# BLOCK4.net
KiCad netlist of a schematic drawn in Altium Designer
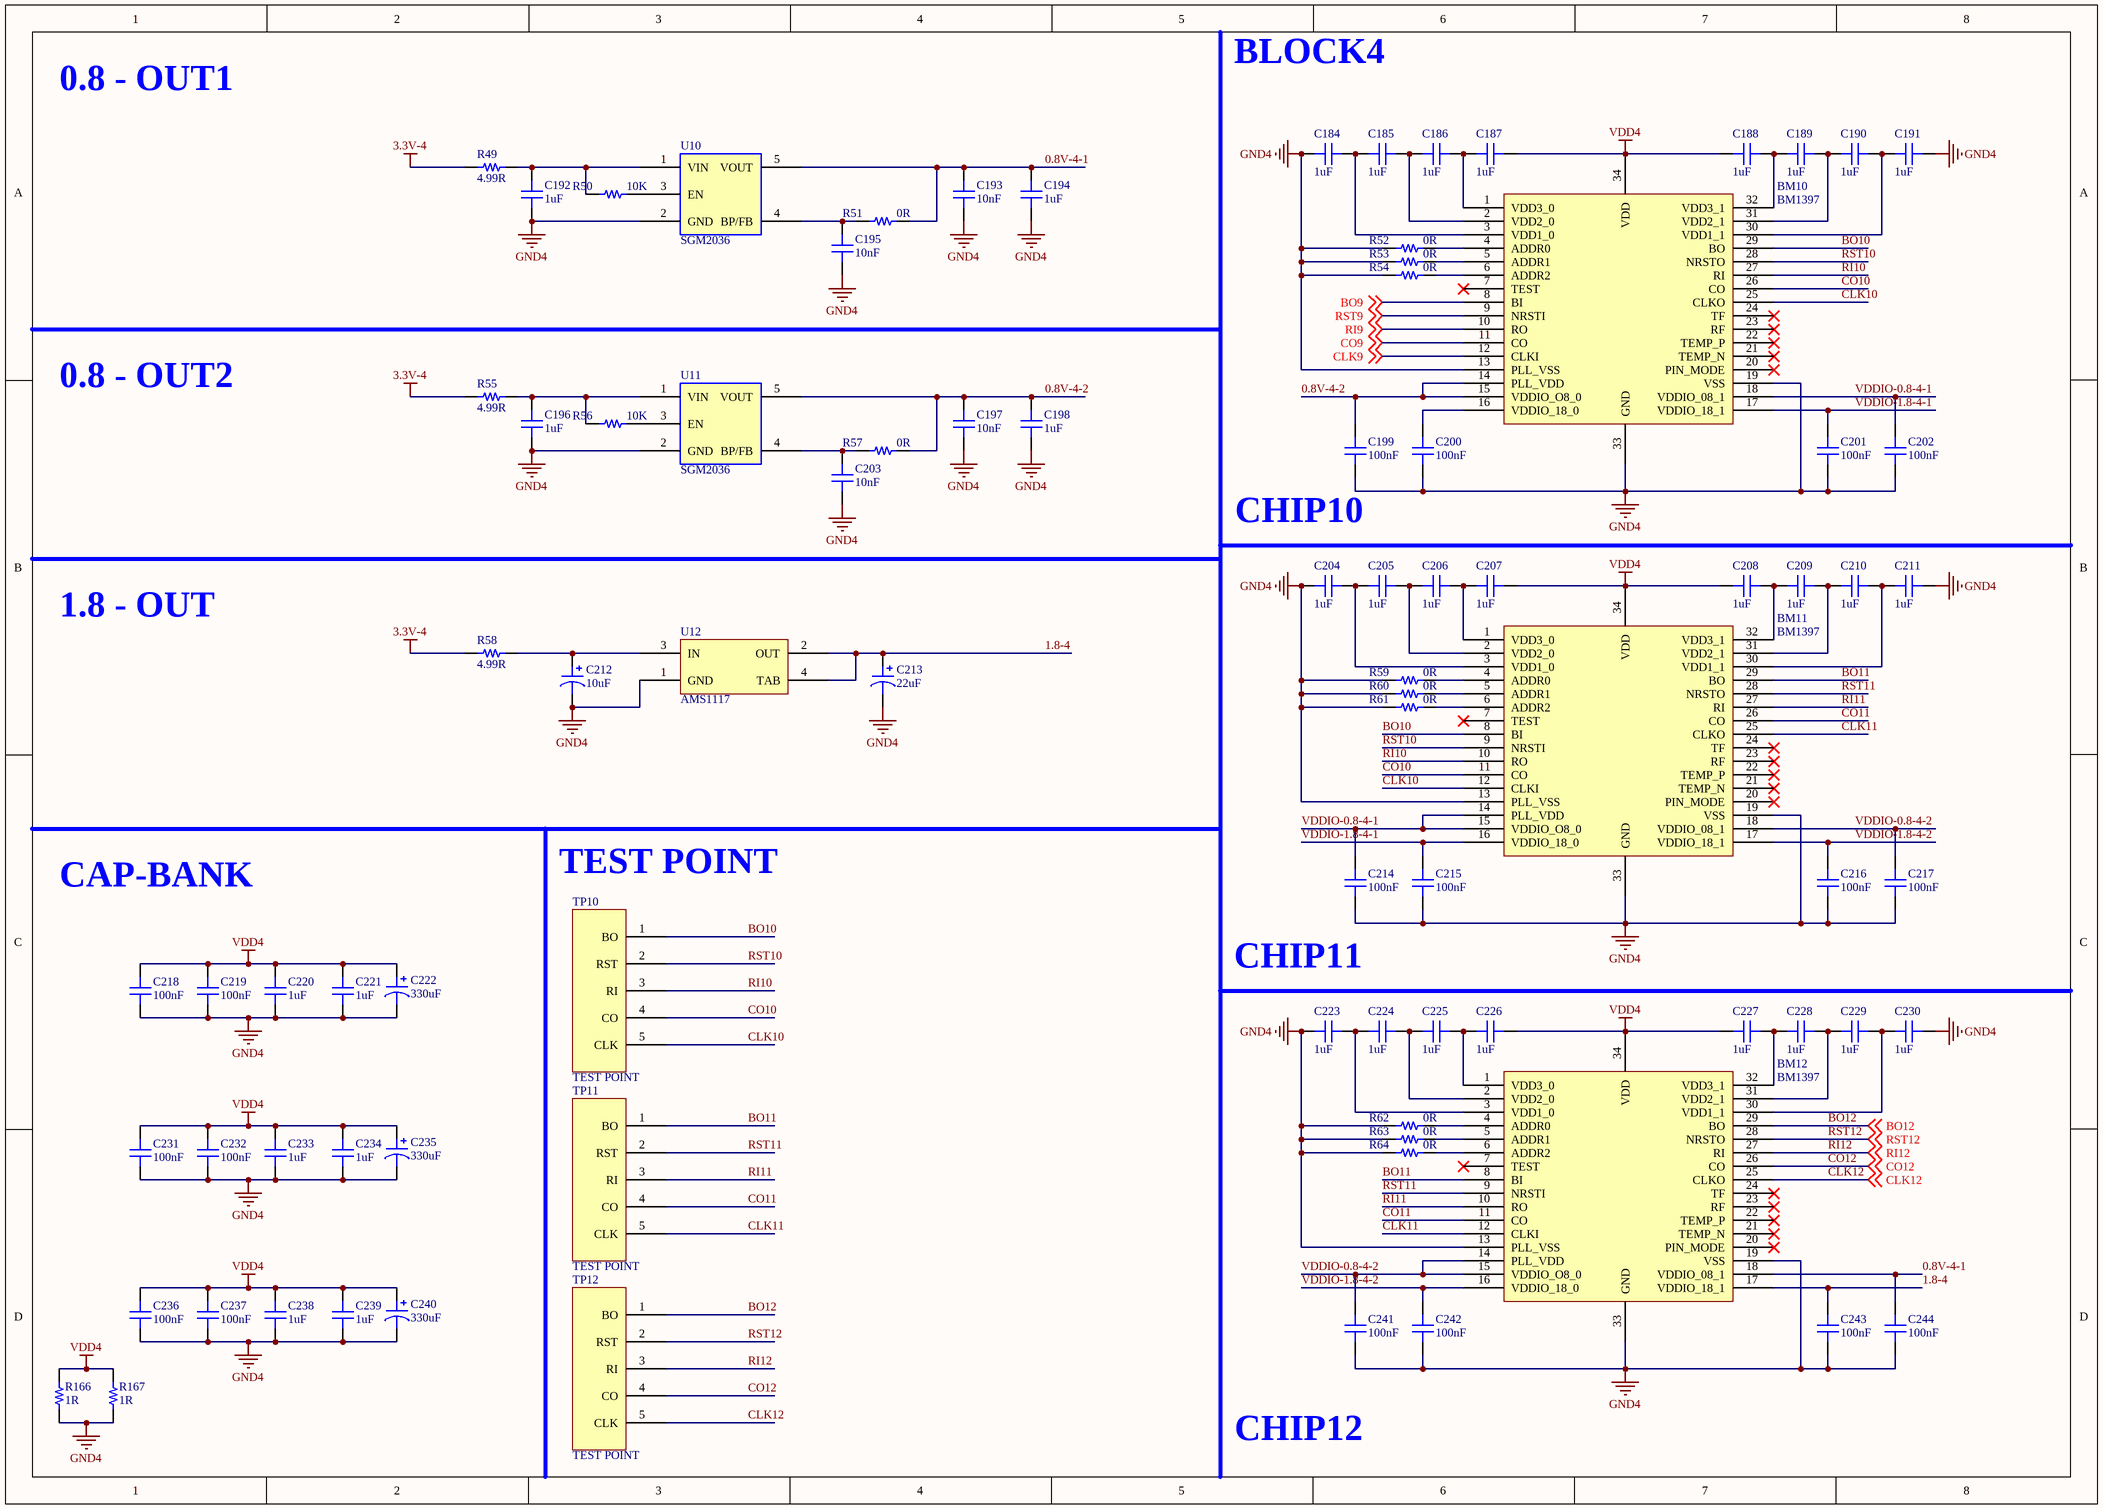
[diagram p0: BLOCK4.SchDoc]

(export (version "E")
  (design (tool "Eeschema 10.0.6"))
  (components
    (comp (ref "BM10") (value "BM1397") (footprint "BM1387") (libsource (lib "Miner_8TH") (part "BM1397_1")))
    (comp (ref "BM11") (value "BM1397") (footprint "BM1387") (libsource (lib "Miner_8TH") (part "BM1397_1")))
    (comp (ref "BM12") (value "BM1397") (footprint "BM1387") (libsource (lib "Miner_8TH") (part "BM1397_1")))
    (comp (ref "C184") (value "1uF") (footprint "CAP-SMD-0603") (libsource (lib "Miner_8TH") (part "CAP")))
    (comp (ref "C185") (value "1uF") (footprint "CAP-SMD-0603") (libsource (lib "Miner_8TH") (part "CAP")))
    (comp (ref "C186") (value "1uF") (footprint "CAP-SMD-0603") (libsource (lib "Miner_8TH") (part "CAP")))
    (comp (ref "C187") (value "1uF") (footprint "CAP-SMD-0603") (libsource (lib "Miner_8TH") (part "CAP")))
    (comp (ref "C188") (value "1uF") (footprint "CAP-SMD-0603") (libsource (lib "Miner_8TH") (part "CAP")))
    (comp (ref "C189") (value "1uF") (footprint "CAP-SMD-0603") (libsource (lib "Miner_8TH") (part "CAP")))
    (comp (ref "C190") (value "1uF") (footprint "CAP-SMD-0603") (libsource (lib "Miner_8TH") (part "CAP")))
    (comp (ref "C191") (value "1uF") (footprint "CAP-SMD-0603") (libsource (lib "Miner_8TH") (part "CAP")))
    (comp (ref "C192") (value "1uF") (footprint "CAP_SMD_0805") (libsource (lib "Miner_8TH") (part "CAP")))
    (comp (ref "C193") (value "10nF") (footprint "CAP_SMD_0805") (libsource (lib "Miner_8TH") (part "CAP")))
    (comp (ref "C194") (value "1uF") (footprint "CAP_SMD_0805") (libsource (lib "Miner_8TH") (part "CAP")))
    (comp (ref "C195") (value "10nF") (footprint "CAP_SMD_0805") (libsource (lib "Miner_8TH") (part "CAP")))
    (comp (ref "C196") (value "1uF") (footprint "CAP_SMD_0805") (libsource (lib "Miner_8TH") (part "CAP")))
    (comp (ref "C197") (value "10nF") (footprint "CAP_SMD_0805") (libsource (lib "Miner_8TH") (part "CAP")))
    (comp (ref "C198") (value "1uF") (footprint "CAP_SMD_0805") (libsource (lib "Miner_8TH") (part "CAP")))
    (comp (ref "C199") (value "100nF") (footprint "CAP_SMD_0805") (libsource (lib "Miner_8TH") (part "CAP")))
    (comp (ref "C200") (value "100nF") (footprint "CAP_SMD_0805") (libsource (lib "Miner_8TH") (part "CAP")))
    (comp (ref "C201") (value "100nF") (footprint "CAP_SMD_0805") (libsource (lib "Miner_8TH") (part "CAP")))
    (comp (ref "C202") (value "100nF") (footprint "CAP_SMD_0805") (libsource (lib "Miner_8TH") (part "CAP")))
    (comp (ref "C203") (value "10nF") (footprint "CAP_SMD_0805") (libsource (lib "Miner_8TH") (part "CAP")))
    (comp (ref "C204") (value "1uF") (footprint "CAP-SMD-0603") (libsource (lib "Miner_8TH") (part "CAP")))
    (comp (ref "C205") (value "1uF") (footprint "CAP-SMD-0603") (libsource (lib "Miner_8TH") (part "CAP")))
    (comp (ref "C206") (value "1uF") (footprint "CAP-SMD-0603") (libsource (lib "Miner_8TH") (part "CAP")))
    (comp (ref "C207") (value "1uF") (footprint "CAP-SMD-0603") (libsource (lib "Miner_8TH") (part "CAP")))
    (comp (ref "C208") (value "1uF") (footprint "CAP-SMD-0603") (libsource (lib "Miner_8TH") (part "CAP")))
    (comp (ref "C209") (value "1uF") (footprint "CAP-SMD-0603") (libsource (lib "Miner_8TH") (part "CAP")))
    (comp (ref "C210") (value "1uF") (footprint "CAP-SMD-0603") (libsource (lib "Miner_8TH") (part "CAP")))
    (comp (ref "C211") (value "1uF") (footprint "CAP-SMD-0603") (libsource (lib "Miner_8TH") (part "CAP")))
    (comp (ref "C212")
      (value "10uF")
      (footprint "CAP-TAN-CASE-A")
      (libsource (lib "Miner_8TH") (part "POLARIZED CAP"))
    )
    (comp (ref "C213")
      (value "22uF")
      (footprint "CAP-TAN-CASE-A")
      (libsource (lib "Miner_8TH") (part "POLARIZED CAP"))
    )
    (comp (ref "C214") (value "100nF") (footprint "CAP_SMD_0805") (libsource (lib "Miner_8TH") (part "CAP")))
    (comp (ref "C215") (value "100nF") (footprint "CAP_SMD_0805") (libsource (lib "Miner_8TH") (part "CAP")))
    (comp (ref "C216") (value "100nF") (footprint "CAP_SMD_0805") (libsource (lib "Miner_8TH") (part "CAP")))
    (comp (ref "C217") (value "100nF") (footprint "CAP_SMD_0805") (libsource (lib "Miner_8TH") (part "CAP")))
    (comp (ref "C218") (value "100nF") (footprint "CAP_SMD_0805") (libsource (lib "Miner_8TH") (part "CAP")))
    (comp (ref "C219") (value "100nF") (footprint "CAP_SMD_0805") (libsource (lib "Miner_8TH") (part "CAP")))
    (comp (ref "C220") (value "1uF") (footprint "CAP_SMD_0805") (libsource (lib "Miner_8TH") (part "CAP")))
    (comp (ref "C221") (value "1uF") (footprint "CAP_SMD_0805") (libsource (lib "Miner_8TH") (part "CAP")))
    (comp (ref "C222")
      (value "330uF")
      (footprint "CAP-TAN-CASE-E")
      (libsource (lib "Miner_8TH") (part "POLARIZED CAP"))
    )
    (comp (ref "C223") (value "1uF") (footprint "CAP-SMD-0603") (libsource (lib "Miner_8TH") (part "CAP")))
    (comp (ref "C224") (value "1uF") (footprint "CAP-SMD-0603") (libsource (lib "Miner_8TH") (part "CAP")))
    (comp (ref "C225") (value "1uF") (footprint "CAP-SMD-0603") (libsource (lib "Miner_8TH") (part "CAP")))
    (comp (ref "C226") (value "1uF") (footprint "CAP-SMD-0603") (libsource (lib "Miner_8TH") (part "CAP")))
    (comp (ref "C227") (value "1uF") (footprint "CAP-SMD-0603") (libsource (lib "Miner_8TH") (part "CAP")))
    (comp (ref "C228") (value "1uF") (footprint "CAP-SMD-0603") (libsource (lib "Miner_8TH") (part "CAP")))
    (comp (ref "C229") (value "1uF") (footprint "CAP-SMD-0603") (libsource (lib "Miner_8TH") (part "CAP")))
    (comp (ref "C230") (value "1uF") (footprint "CAP-SMD-0603") (libsource (lib "Miner_8TH") (part "CAP")))
    (comp (ref "C231") (value "100nF") (footprint "CAP_SMD_0805") (libsource (lib "Miner_8TH") (part "CAP")))
    (comp (ref "C232") (value "100nF") (footprint "CAP_SMD_0805") (libsource (lib "Miner_8TH") (part "CAP")))
    (comp (ref "C233") (value "1uF") (footprint "CAP_SMD_0805") (libsource (lib "Miner_8TH") (part "CAP")))
    (comp (ref "C234") (value "1uF") (footprint "CAP_SMD_0805") (libsource (lib "Miner_8TH") (part "CAP")))
    (comp (ref "C235")
      (value "330uF")
      (footprint "CAP-TAN-CASE-E")
      (libsource (lib "Miner_8TH") (part "POLARIZED CAP"))
    )
    (comp (ref "C236") (value "100nF") (footprint "CAP_SMD_0805") (libsource (lib "Miner_8TH") (part "CAP")))
    (comp (ref "C237") (value "100nF") (footprint "CAP_SMD_0805") (libsource (lib "Miner_8TH") (part "CAP")))
    (comp (ref "C238") (value "1uF") (footprint "CAP_SMD_0805") (libsource (lib "Miner_8TH") (part "CAP")))
    (comp (ref "C239") (value "1uF") (footprint "CAP_SMD_0805") (libsource (lib "Miner_8TH") (part "CAP")))
    (comp (ref "C240")
      (value "330uF")
      (footprint "CAP-TAN-CASE-E")
      (libsource (lib "Miner_8TH") (part "POLARIZED CAP"))
    )
    (comp (ref "C241") (value "100nF") (footprint "CAP_SMD_0805") (libsource (lib "Miner_8TH") (part "CAP")))
    (comp (ref "C242") (value "100nF") (footprint "CAP_SMD_0805") (libsource (lib "Miner_8TH") (part "CAP")))
    (comp (ref "C243") (value "100nF") (footprint "CAP_SMD_0805") (libsource (lib "Miner_8TH") (part "CAP")))
    (comp (ref "C244") (value "100nF") (footprint "CAP_SMD_0805") (libsource (lib "Miner_8TH") (part "CAP")))
    (comp (ref "R49") (value "4.99R") (footprint "RES-SMD-1206") (libsource (lib "Miner_8TH") (part "RES")))
    (comp (ref "R50") (value "10K") (footprint "RES-SMD-0402") (libsource (lib "Miner_8TH") (part "RES")))
    (comp (ref "R51") (value "0R") (footprint "RES-SMD-0402") (libsource (lib "Miner_8TH") (part "RES")))
    (comp (ref "R52") (value "0R") (footprint "RES-SMD-0402") (libsource (lib "Miner_8TH") (part "RES")))
    (comp (ref "R53") (value "0R") (footprint "RES-SMD-0402") (libsource (lib "Miner_8TH") (part "RES")))
    (comp (ref "R54") (value "0R") (footprint "RES-SMD-0402") (libsource (lib "Miner_8TH") (part "RES")))
    (comp (ref "R55") (value "4.99R") (footprint "RES-SMD-1206") (libsource (lib "Miner_8TH") (part "RES")))
    (comp (ref "R56") (value "10K") (footprint "RES-SMD-0402") (libsource (lib "Miner_8TH") (part "RES")))
    (comp (ref "R57") (value "0R") (footprint "RES-SMD-0402") (libsource (lib "Miner_8TH") (part "RES")))
    (comp (ref "R58") (value "4.99R") (footprint "RES-SMD-1206") (libsource (lib "Miner_8TH") (part "RES")))
    (comp (ref "R59") (value "0R") (footprint "RES-SMD-0402") (libsource (lib "Miner_8TH") (part "RES")))
    (comp (ref "R60") (value "0R") (footprint "RES-SMD-0402") (libsource (lib "Miner_8TH") (part "RES")))
    (comp (ref "R61") (value "0R") (footprint "RES-SMD-0402") (libsource (lib "Miner_8TH") (part "RES")))
    (comp (ref "R62") (value "0R") (footprint "RES-SMD-0402") (libsource (lib "Miner_8TH") (part "RES")))
    (comp (ref "R63") (value "0R") (footprint "RES-SMD-0402") (libsource (lib "Miner_8TH") (part "RES")))
    (comp (ref "R64") (value "0R") (footprint "RES-SMD-0402") (libsource (lib "Miner_8TH") (part "RES")))
    (comp (ref "R166") (value "1R") (footprint "RES-SMD-1210") (libsource (lib "Miner_8TH") (part "RES")))
    (comp (ref "R167") (value "1R") (footprint "RES-SMD-1210") (libsource (lib "Miner_8TH") (part "RES")))
    (comp (ref "TP10")
      (value "TEST POINT")
      (footprint "TEST_POINT")
      (libsource (lib "Miner_8TH") (part "TEST POINT"))
    )
    (comp (ref "TP11")
      (value "TEST POINT")
      (footprint "TEST_POINT")
      (libsource (lib "Miner_8TH") (part "TEST POINT"))
    )
    (comp (ref "TP12")
      (value "TEST POINT")
      (footprint "TEST_POINT")
      (libsource (lib "Miner_8TH") (part "TEST POINT"))
    )
    (comp (ref "U10")
      (value "SGM2036")
      (footprint "SOT23-5PIN")
      (libsource (lib "Miner_8TH") (part "SGM2036"))
    )
    (comp (ref "U11")
      (value "SGM2036")
      (footprint "SOT23-5PIN")
      (libsource (lib "Miner_8TH") (part "SGM2036"))
    )
    (comp (ref "U12") (value "AMS1117") (footprint "AMS1117") (libsource (lib "Miner_8TH") (part "AMS1117")))
  )
  (nets
    (net (code "1") (name "/0.8V-4-1") (class "Default")
      (node (ref "BM12") (pin "18") (pinfunction "VDDIO_08_1_18") (pintype "passive"))
      (node (ref "C193") (pin "2") (pinfunction "2_2") (pintype "passive"))
      (node (ref "C194") (pin "2") (pinfunction "2_2") (pintype "passive"))
      (node (ref "C244") (pin "2") (pinfunction "2_2") (pintype "passive"))
      (node (ref "R51") (pin "2") (pinfunction "2_2") (pintype "passive"))
      (node (ref "U10") (pin "5") (pinfunction "VOUT_5") (pintype "passive"))
    )
    (net (code "2") (name "/0.8V-4-2") (class "Default")
      (node (ref "BM10") (pin "14") (pinfunction "PLL_VDD_14") (pintype "passive"))
      (node (ref "BM10") (pin "15") (pinfunction "VDDIO_O8_0_15") (pintype "passive"))
      (node (ref "C197") (pin "2") (pinfunction "2_2") (pintype "passive"))
      (node (ref "C198") (pin "2") (pinfunction "2_2") (pintype "passive"))
      (node (ref "C199") (pin "2") (pinfunction "2_2") (pintype "passive"))
      (node (ref "R57") (pin "2") (pinfunction "2_2") (pintype "passive"))
      (node (ref "U11") (pin "5") (pinfunction "VOUT_5") (pintype "passive"))
    )
    (net (code "3") (name "/1.8-4") (class "Default")
      (node (ref "BM12") (pin "17") (pinfunction "VDDIO_18_1_17") (pintype "passive"))
      (node (ref "C213") (pin "1") (pinfunction "1_1") (pintype "passive"))
      (node (ref "C243") (pin "2") (pinfunction "2_2") (pintype "passive"))
      (node (ref "U12") (pin "2") (pinfunction "OUT_2") (pintype "passive"))
      (node (ref "U12") (pin "4") (pinfunction "TAB_4") (pintype "passive"))
    )
    (net (code "4") (name "/BO10") (class "Default")
      (node (ref "BM10") (pin "29") (pinfunction "BO_29") (pintype "passive"))
      (node (ref "BM11") (pin "8") (pinfunction "BI_8") (pintype "passive"))
      (node (ref "TP10") (pin "1") (pinfunction "BO_1") (pintype "passive"))
    )
    (net (code "5") (name "/BO11") (class "Default")
      (node (ref "BM11") (pin "29") (pinfunction "BO_29") (pintype "passive"))
      (node (ref "BM12") (pin "8") (pinfunction "BI_8") (pintype "passive"))
      (node (ref "TP11") (pin "1") (pinfunction "BO_1") (pintype "passive"))
    )
    (net (code "6") (name "/CLK10") (class "Default")
      (node (ref "BM10") (pin "25") (pinfunction "CLKO_25") (pintype "passive"))
      (node (ref "BM11") (pin "12") (pinfunction "CLKI_12") (pintype "passive"))
      (node (ref "TP10") (pin "5") (pinfunction "CLK_5") (pintype "passive"))
    )
    (net (code "7") (name "/CLK11") (class "Default")
      (node (ref "BM11") (pin "25") (pinfunction "CLKO_25") (pintype "passive"))
      (node (ref "BM12") (pin "12") (pinfunction "CLKI_12") (pintype "passive"))
      (node (ref "TP11") (pin "5") (pinfunction "CLK_5") (pintype "passive"))
    )
    (net (code "8") (name "/CO10") (class "Default")
      (node (ref "BM10") (pin "26") (pinfunction "CO_26") (pintype "passive"))
      (node (ref "BM11") (pin "11") (pinfunction "CO_11") (pintype "passive"))
      (node (ref "TP10") (pin "4") (pinfunction "CO_4") (pintype "passive"))
    )
    (net (code "9") (name "/CO11") (class "Default")
      (node (ref "BM11") (pin "26") (pinfunction "CO_26") (pintype "passive"))
      (node (ref "BM12") (pin "11") (pinfunction "CO_11") (pintype "passive"))
      (node (ref "TP11") (pin "4") (pinfunction "CO_4") (pintype "passive"))
    )
    (net (code "10") (name "/RI10") (class "Default")
      (node (ref "BM10") (pin "27") (pinfunction "RI_27") (pintype "passive"))
      (node (ref "BM11") (pin "10") (pinfunction "RO_10") (pintype "passive"))
      (node (ref "TP10") (pin "3") (pinfunction "RI_3") (pintype "passive"))
    )
    (net (code "11") (name "/RI11") (class "Default")
      (node (ref "BM11") (pin "27") (pinfunction "RI_27") (pintype "passive"))
      (node (ref "BM12") (pin "10") (pinfunction "RO_10") (pintype "passive"))
      (node (ref "TP11") (pin "3") (pinfunction "RI_3") (pintype "passive"))
    )
    (net (code "12") (name "/RST10") (class "Default")
      (node (ref "BM10") (pin "28") (pinfunction "NRSTO_28") (pintype "passive"))
      (node (ref "BM11") (pin "9") (pinfunction "NRSTI_9") (pintype "passive"))
      (node (ref "TP10") (pin "2") (pinfunction "RST_2") (pintype "passive"))
    )
    (net (code "13") (name "/RST11") (class "Default")
      (node (ref "BM11") (pin "28") (pinfunction "NRSTO_28") (pintype "passive"))
      (node (ref "BM12") (pin "9") (pinfunction "NRSTI_9") (pintype "passive"))
      (node (ref "TP11") (pin "2") (pinfunction "RST_2") (pintype "passive"))
    )
    (net (code "14") (name "/VDDIO-0.8-4-1") (class "Default")
      (node (ref "BM10") (pin "18") (pinfunction "VDDIO_08_1_18") (pintype "passive"))
      (node (ref "BM11") (pin "14") (pinfunction "PLL_VDD_14") (pintype "passive"))
      (node (ref "BM11") (pin "15") (pinfunction "VDDIO_O8_0_15") (pintype "passive"))
      (node (ref "C202") (pin "2") (pinfunction "2_2") (pintype "passive"))
      (node (ref "C214") (pin "2") (pinfunction "2_2") (pintype "passive"))
    )
    (net (code "15") (name "/VDDIO-0.8-4-2") (class "Default")
      (node (ref "BM11") (pin "18") (pinfunction "VDDIO_08_1_18") (pintype "passive"))
      (node (ref "BM12") (pin "14") (pinfunction "PLL_VDD_14") (pintype "passive"))
      (node (ref "BM12") (pin "15") (pinfunction "VDDIO_O8_0_15") (pintype "passive"))
      (node (ref "C217") (pin "2") (pinfunction "2_2") (pintype "passive"))
      (node (ref "C241") (pin "2") (pinfunction "2_2") (pintype "passive"))
    )
    (net (code "16") (name "/VDDIO-1.8-4-1") (class "Default")
      (node (ref "BM10") (pin "17") (pinfunction "VDDIO_18_1_17") (pintype "passive"))
      (node (ref "BM11") (pin "16") (pinfunction "VDDIO_18_0_16") (pintype "passive"))
      (node (ref "C201") (pin "2") (pinfunction "2_2") (pintype "passive"))
      (node (ref "C215") (pin "2") (pinfunction "2_2") (pintype "passive"))
    )
    (net (code "17") (name "/VDDIO-1.8-4-2") (class "Default")
      (node (ref "BM11") (pin "17") (pinfunction "VDDIO_18_1_17") (pintype "passive"))
      (node (ref "BM12") (pin "16") (pinfunction "VDDIO_18_0_16") (pintype "passive"))
      (node (ref "C216") (pin "2") (pinfunction "2_2") (pintype "passive"))
      (node (ref "C242") (pin "2") (pinfunction "2_2") (pintype "passive"))
    )
    (net (code "18") (name "3.3V-4") (class "Default")
      (node (ref "R49") (pin "1") (pinfunction "1_1") (pintype "passive"))
      (node (ref "R55") (pin "1") (pinfunction "1_1") (pintype "passive"))
      (node (ref "R58") (pin "1") (pinfunction "1_1") (pintype "passive"))
    )
    (net (code "19") (name "BO9") (class "Default")
      (node (ref "BM10") (pin "8") (pinfunction "BI_8") (pintype "passive"))
    )
    (net (code "20") (name "BO12") (class "Default")
      (node (ref "BM12") (pin "29") (pinfunction "BO_29") (pintype "passive"))
      (node (ref "TP12") (pin "1") (pinfunction "BO_1") (pintype "passive"))
    )
    (net (code "21") (name "CLK9") (class "Default")
      (node (ref "BM10") (pin "12") (pinfunction "CLKI_12") (pintype "passive"))
    )
    (net (code "22") (name "CLK12") (class "Default")
      (node (ref "BM12") (pin "25") (pinfunction "CLKO_25") (pintype "passive"))
      (node (ref "TP12") (pin "5") (pinfunction "CLK_5") (pintype "passive"))
    )
    (net (code "23") (name "CO9") (class "Default")
      (node (ref "BM10") (pin "11") (pinfunction "CO_11") (pintype "passive"))
    )
    (net (code "24") (name "CO12") (class "Default")
      (node (ref "BM12") (pin "26") (pinfunction "CO_26") (pintype "passive"))
      (node (ref "TP12") (pin "4") (pinfunction "CO_4") (pintype "passive"))
    )
    (net (code "25") (name "GND4") (class "Default")
      (node (ref "BM10") (pin "13") (pinfunction "PLL_VSS_13") (pintype "passive"))
      (node (ref "BM10") (pin "19") (pinfunction "VSS_19") (pintype "passive"))
      (node (ref "BM10") (pin "33") (pinfunction "GND_33") (pintype "passive"))
      (node (ref "BM11") (pin "13") (pinfunction "PLL_VSS_13") (pintype "passive"))
      (node (ref "BM11") (pin "19") (pinfunction "VSS_19") (pintype "passive"))
      (node (ref "BM11") (pin "33") (pinfunction "GND_33") (pintype "passive"))
      (node (ref "BM12") (pin "13") (pinfunction "PLL_VSS_13") (pintype "passive"))
      (node (ref "BM12") (pin "19") (pinfunction "VSS_19") (pintype "passive"))
      (node (ref "BM12") (pin "33") (pinfunction "GND_33") (pintype "passive"))
      (node (ref "C184") (pin "1") (pinfunction "1_1") (pintype "passive"))
      (node (ref "C191") (pin "2") (pinfunction "2_2") (pintype "passive"))
      (node (ref "C192") (pin "1") (pinfunction "1_1") (pintype "passive"))
      (node (ref "C193") (pin "1") (pinfunction "1_1") (pintype "passive"))
      (node (ref "C194") (pin "1") (pinfunction "1_1") (pintype "passive"))
      (node (ref "C195") (pin "1") (pinfunction "1_1") (pintype "passive"))
      (node (ref "C196") (pin "1") (pinfunction "1_1") (pintype "passive"))
      (node (ref "C197") (pin "1") (pinfunction "1_1") (pintype "passive"))
      (node (ref "C198") (pin "1") (pinfunction "1_1") (pintype "passive"))
      (node (ref "C199") (pin "1") (pinfunction "1_1") (pintype "passive"))
      (node (ref "C200") (pin "1") (pinfunction "1_1") (pintype "passive"))
      (node (ref "C201") (pin "1") (pinfunction "1_1") (pintype "passive"))
      (node (ref "C202") (pin "1") (pinfunction "1_1") (pintype "passive"))
      (node (ref "C203") (pin "1") (pinfunction "1_1") (pintype "passive"))
      (node (ref "C204") (pin "1") (pinfunction "1_1") (pintype "passive"))
      (node (ref "C211") (pin "2") (pinfunction "2_2") (pintype "passive"))
      (node (ref "C212") (pin "2") (pinfunction "2_2") (pintype "passive"))
      (node (ref "C213") (pin "2") (pinfunction "2_2") (pintype "passive"))
      (node (ref "C214") (pin "1") (pinfunction "1_1") (pintype "passive"))
      (node (ref "C215") (pin "1") (pinfunction "1_1") (pintype "passive"))
      (node (ref "C216") (pin "1") (pinfunction "1_1") (pintype "passive"))
      (node (ref "C217") (pin "1") (pinfunction "1_1") (pintype "passive"))
      (node (ref "C218") (pin "1") (pinfunction "1_1") (pintype "passive"))
      (node (ref "C219") (pin "1") (pinfunction "1_1") (pintype "passive"))
      (node (ref "C220") (pin "1") (pinfunction "1_1") (pintype "passive"))
      (node (ref "C221") (pin "1") (pinfunction "1_1") (pintype "passive"))
      (node (ref "C222") (pin "2") (pinfunction "2_2") (pintype "passive"))
      (node (ref "C223") (pin "1") (pinfunction "1_1") (pintype "passive"))
      (node (ref "C230") (pin "2") (pinfunction "2_2") (pintype "passive"))
      (node (ref "C231") (pin "1") (pinfunction "1_1") (pintype "passive"))
      (node (ref "C232") (pin "1") (pinfunction "1_1") (pintype "passive"))
      (node (ref "C233") (pin "1") (pinfunction "1_1") (pintype "passive"))
      (node (ref "C234") (pin "1") (pinfunction "1_1") (pintype "passive"))
      (node (ref "C235") (pin "2") (pinfunction "2_2") (pintype "passive"))
      (node (ref "C236") (pin "1") (pinfunction "1_1") (pintype "passive"))
      (node (ref "C237") (pin "1") (pinfunction "1_1") (pintype "passive"))
      (node (ref "C238") (pin "1") (pinfunction "1_1") (pintype "passive"))
      (node (ref "C239") (pin "1") (pinfunction "1_1") (pintype "passive"))
      (node (ref "C240") (pin "2") (pinfunction "2_2") (pintype "passive"))
      (node (ref "C241") (pin "1") (pinfunction "1_1") (pintype "passive"))
      (node (ref "C242") (pin "1") (pinfunction "1_1") (pintype "passive"))
      (node (ref "C243") (pin "1") (pinfunction "1_1") (pintype "passive"))
      (node (ref "C244") (pin "1") (pinfunction "1_1") (pintype "passive"))
      (node (ref "R166") (pin "1") (pinfunction "1_1") (pintype "passive"))
      (node (ref "R167") (pin "1") (pinfunction "1_1") (pintype "passive"))
      (node (ref "R52") (pin "1") (pinfunction "1_1") (pintype "passive"))
      (node (ref "R53") (pin "1") (pinfunction "1_1") (pintype "passive"))
      (node (ref "R54") (pin "1") (pinfunction "1_1") (pintype "passive"))
      (node (ref "R59") (pin "1") (pinfunction "1_1") (pintype "passive"))
      (node (ref "R60") (pin "1") (pinfunction "1_1") (pintype "passive"))
      (node (ref "R61") (pin "1") (pinfunction "1_1") (pintype "passive"))
      (node (ref "R62") (pin "1") (pinfunction "1_1") (pintype "passive"))
      (node (ref "R63") (pin "1") (pinfunction "1_1") (pintype "passive"))
      (node (ref "R64") (pin "1") (pinfunction "1_1") (pintype "passive"))
      (node (ref "U10") (pin "2") (pinfunction "GND_2") (pintype "passive"))
      (node (ref "U11") (pin "2") (pinfunction "GND_2") (pintype "passive"))
      (node (ref "U12") (pin "1") (pinfunction "GND_1") (pintype "passive"))
    )
    (net (code "26") (name "Net-(BM10-ADDR0)") (class "Default")
      (node (ref "BM10") (pin "4") (pinfunction "ADDR0_4") (pintype "passive"))
      (node (ref "R52") (pin "2") (pinfunction "2_2") (pintype "passive"))
    )
    (net (code "27") (name "Net-(BM10-ADDR1)") (class "Default")
      (node (ref "BM10") (pin "5") (pinfunction "ADDR1_5") (pintype "passive"))
      (node (ref "R53") (pin "2") (pinfunction "2_2") (pintype "passive"))
    )
    (net (code "28") (name "Net-(BM10-ADDR2)") (class "Default")
      (node (ref "BM10") (pin "6") (pinfunction "ADDR2_6") (pintype "passive"))
      (node (ref "R54") (pin "2") (pinfunction "2_2") (pintype "passive"))
    )
    (net (code "29") (name "Net-(BM10-VDD1_0)") (class "Default")
      (node (ref "BM10") (pin "3") (pinfunction "VDD1_0_3") (pintype "passive"))
      (node (ref "C184") (pin "2") (pinfunction "2_2") (pintype "passive"))
      (node (ref "C185") (pin "1") (pinfunction "1_1") (pintype "passive"))
    )
    (net (code "30") (name "Net-(BM10-VDD1_1)") (class "Default")
      (node (ref "BM10") (pin "30") (pinfunction "VDD1_1_30") (pintype "passive"))
      (node (ref "C190") (pin "2") (pinfunction "2_2") (pintype "passive"))
      (node (ref "C191") (pin "1") (pinfunction "1_1") (pintype "passive"))
    )
    (net (code "31") (name "Net-(BM10-VDD2_0)") (class "Default")
      (node (ref "BM10") (pin "2") (pinfunction "VDD2_0_2") (pintype "passive"))
      (node (ref "C185") (pin "2") (pinfunction "2_2") (pintype "passive"))
      (node (ref "C186") (pin "1") (pinfunction "1_1") (pintype "passive"))
    )
    (net (code "32") (name "Net-(BM10-VDD2_1)") (class "Default")
      (node (ref "BM10") (pin "31") (pinfunction "VDD2_1_31") (pintype "passive"))
      (node (ref "C189") (pin "2") (pinfunction "2_2") (pintype "passive"))
      (node (ref "C190") (pin "1") (pinfunction "1_1") (pintype "passive"))
    )
    (net (code "33") (name "Net-(BM10-VDD3_0)") (class "Default")
      (node (ref "BM10") (pin "1") (pinfunction "VDD3_0_1") (pintype "passive"))
      (node (ref "C186") (pin "2") (pinfunction "2_2") (pintype "passive"))
      (node (ref "C187") (pin "1") (pinfunction "1_1") (pintype "passive"))
    )
    (net (code "34") (name "Net-(BM10-VDD3_1)") (class "Default")
      (node (ref "BM10") (pin "32") (pinfunction "VDD3_1_32") (pintype "passive"))
      (node (ref "C188") (pin "2") (pinfunction "2_2") (pintype "passive"))
      (node (ref "C189") (pin "1") (pinfunction "1_1") (pintype "passive"))
    )
    (net (code "35") (name "Net-(BM10-VDDIO_18_0)") (class "Default")
      (node (ref "BM10") (pin "16") (pinfunction "VDDIO_18_0_16") (pintype "passive"))
      (node (ref "C200") (pin "2") (pinfunction "2_2") (pintype "passive"))
    )
    (net (code "36") (name "Net-(BM11-ADDR0)") (class "Default")
      (node (ref "BM11") (pin "4") (pinfunction "ADDR0_4") (pintype "passive"))
      (node (ref "R59") (pin "2") (pinfunction "2_2") (pintype "passive"))
    )
    (net (code "37") (name "Net-(BM11-ADDR1)") (class "Default")
      (node (ref "BM11") (pin "5") (pinfunction "ADDR1_5") (pintype "passive"))
      (node (ref "R60") (pin "2") (pinfunction "2_2") (pintype "passive"))
    )
    (net (code "38") (name "Net-(BM11-ADDR2)") (class "Default")
      (node (ref "BM11") (pin "6") (pinfunction "ADDR2_6") (pintype "passive"))
      (node (ref "R61") (pin "2") (pinfunction "2_2") (pintype "passive"))
    )
    (net (code "39") (name "Net-(BM11-VDD1_0)") (class "Default")
      (node (ref "BM11") (pin "3") (pinfunction "VDD1_0_3") (pintype "passive"))
      (node (ref "C204") (pin "2") (pinfunction "2_2") (pintype "passive"))
      (node (ref "C205") (pin "1") (pinfunction "1_1") (pintype "passive"))
    )
    (net (code "40") (name "Net-(BM11-VDD1_1)") (class "Default")
      (node (ref "BM11") (pin "30") (pinfunction "VDD1_1_30") (pintype "passive"))
      (node (ref "C210") (pin "2") (pinfunction "2_2") (pintype "passive"))
      (node (ref "C211") (pin "1") (pinfunction "1_1") (pintype "passive"))
    )
    (net (code "41") (name "Net-(BM11-VDD2_0)") (class "Default")
      (node (ref "BM11") (pin "2") (pinfunction "VDD2_0_2") (pintype "passive"))
      (node (ref "C205") (pin "2") (pinfunction "2_2") (pintype "passive"))
      (node (ref "C206") (pin "1") (pinfunction "1_1") (pintype "passive"))
    )
    (net (code "42") (name "Net-(BM11-VDD2_1)") (class "Default")
      (node (ref "BM11") (pin "31") (pinfunction "VDD2_1_31") (pintype "passive"))
      (node (ref "C209") (pin "2") (pinfunction "2_2") (pintype "passive"))
      (node (ref "C210") (pin "1") (pinfunction "1_1") (pintype "passive"))
    )
    (net (code "43") (name "Net-(BM11-VDD3_0)") (class "Default")
      (node (ref "BM11") (pin "1") (pinfunction "VDD3_0_1") (pintype "passive"))
      (node (ref "C206") (pin "2") (pinfunction "2_2") (pintype "passive"))
      (node (ref "C207") (pin "1") (pinfunction "1_1") (pintype "passive"))
    )
    (net (code "44") (name "Net-(BM11-VDD3_1)") (class "Default")
      (node (ref "BM11") (pin "32") (pinfunction "VDD3_1_32") (pintype "passive"))
      (node (ref "C208") (pin "2") (pinfunction "2_2") (pintype "passive"))
      (node (ref "C209") (pin "1") (pinfunction "1_1") (pintype "passive"))
    )
    (net (code "45") (name "Net-(BM12-ADDR0)") (class "Default")
      (node (ref "BM12") (pin "4") (pinfunction "ADDR0_4") (pintype "passive"))
      (node (ref "R62") (pin "2") (pinfunction "2_2") (pintype "passive"))
    )
    (net (code "46") (name "Net-(BM12-ADDR1)") (class "Default")
      (node (ref "BM12") (pin "5") (pinfunction "ADDR1_5") (pintype "passive"))
      (node (ref "R63") (pin "2") (pinfunction "2_2") (pintype "passive"))
    )
    (net (code "47") (name "Net-(BM12-ADDR2)") (class "Default")
      (node (ref "BM12") (pin "6") (pinfunction "ADDR2_6") (pintype "passive"))
      (node (ref "R64") (pin "2") (pinfunction "2_2") (pintype "passive"))
    )
    (net (code "48") (name "Net-(BM12-VDD1_0)") (class "Default")
      (node (ref "BM12") (pin "3") (pinfunction "VDD1_0_3") (pintype "passive"))
      (node (ref "C223") (pin "2") (pinfunction "2_2") (pintype "passive"))
      (node (ref "C224") (pin "1") (pinfunction "1_1") (pintype "passive"))
    )
    (net (code "49") (name "Net-(BM12-VDD1_1)") (class "Default")
      (node (ref "BM12") (pin "30") (pinfunction "VDD1_1_30") (pintype "passive"))
      (node (ref "C229") (pin "2") (pinfunction "2_2") (pintype "passive"))
      (node (ref "C230") (pin "1") (pinfunction "1_1") (pintype "passive"))
    )
    (net (code "50") (name "Net-(BM12-VDD2_0)") (class "Default")
      (node (ref "BM12") (pin "2") (pinfunction "VDD2_0_2") (pintype "passive"))
      (node (ref "C224") (pin "2") (pinfunction "2_2") (pintype "passive"))
      (node (ref "C225") (pin "1") (pinfunction "1_1") (pintype "passive"))
    )
    (net (code "51") (name "Net-(BM12-VDD2_1)") (class "Default")
      (node (ref "BM12") (pin "31") (pinfunction "VDD2_1_31") (pintype "passive"))
      (node (ref "C228") (pin "2") (pinfunction "2_2") (pintype "passive"))
      (node (ref "C229") (pin "1") (pinfunction "1_1") (pintype "passive"))
    )
    (net (code "52") (name "Net-(BM12-VDD3_0)") (class "Default")
      (node (ref "BM12") (pin "1") (pinfunction "VDD3_0_1") (pintype "passive"))
      (node (ref "C225") (pin "2") (pinfunction "2_2") (pintype "passive"))
      (node (ref "C226") (pin "1") (pinfunction "1_1") (pintype "passive"))
    )
    (net (code "53") (name "Net-(BM12-VDD3_1)") (class "Default")
      (node (ref "BM12") (pin "32") (pinfunction "VDD3_1_32") (pintype "passive"))
      (node (ref "C227") (pin "2") (pinfunction "2_2") (pintype "passive"))
      (node (ref "C228") (pin "1") (pinfunction "1_1") (pintype "passive"))
    )
    (net (code "54") (name "Net-(U10-BP{slash}FB)") (class "Default")
      (node (ref "C195") (pin "2") (pinfunction "2_2") (pintype "passive"))
      (node (ref "R51") (pin "1") (pinfunction "1_1") (pintype "passive"))
      (node (ref "U10") (pin "4") (pinfunction "BP/FB_4") (pintype "passive"))
    )
    (net (code "55") (name "Net-(U10-EN)") (class "Default")
      (node (ref "R50") (pin "2") (pinfunction "2_2") (pintype "passive"))
      (node (ref "U10") (pin "3") (pinfunction "EN_3") (pintype "passive"))
    )
    (net (code "56") (name "Net-(U10-VIN)") (class "Default")
      (node (ref "C192") (pin "2") (pinfunction "2_2") (pintype "passive"))
      (node (ref "R49") (pin "2") (pinfunction "2_2") (pintype "passive"))
      (node (ref "R50") (pin "1") (pinfunction "1_1") (pintype "passive"))
      (node (ref "U10") (pin "1") (pinfunction "VIN_1") (pintype "passive"))
    )
    (net (code "57") (name "Net-(U11-BP{slash}FB)") (class "Default")
      (node (ref "C203") (pin "2") (pinfunction "2_2") (pintype "passive"))
      (node (ref "R57") (pin "1") (pinfunction "1_1") (pintype "passive"))
      (node (ref "U11") (pin "4") (pinfunction "BP/FB_4") (pintype "passive"))
    )
    (net (code "58") (name "Net-(U11-EN)") (class "Default")
      (node (ref "R56") (pin "2") (pinfunction "2_2") (pintype "passive"))
      (node (ref "U11") (pin "3") (pinfunction "EN_3") (pintype "passive"))
    )
    (net (code "59") (name "Net-(U11-VIN)") (class "Default")
      (node (ref "C196") (pin "2") (pinfunction "2_2") (pintype "passive"))
      (node (ref "R55") (pin "2") (pinfunction "2_2") (pintype "passive"))
      (node (ref "R56") (pin "1") (pinfunction "1_1") (pintype "passive"))
      (node (ref "U11") (pin "1") (pinfunction "VIN_1") (pintype "passive"))
    )
    (net (code "60") (name "Net-(U12-IN)") (class "Default")
      (node (ref "C212") (pin "1") (pinfunction "1_1") (pintype "passive"))
      (node (ref "R58") (pin "2") (pinfunction "2_2") (pintype "passive"))
      (node (ref "U12") (pin "3") (pinfunction "IN_3") (pintype "passive"))
    )
    (net (code "61") (name "RI9") (class "Default")
      (node (ref "BM10") (pin "10") (pinfunction "RO_10") (pintype "passive"))
    )
    (net (code "62") (name "RI12") (class "Default")
      (node (ref "BM12") (pin "27") (pinfunction "RI_27") (pintype "passive"))
      (node (ref "TP12") (pin "3") (pinfunction "RI_3") (pintype "passive"))
    )
    (net (code "63") (name "RST9") (class "Default")
      (node (ref "BM10") (pin "9") (pinfunction "NRSTI_9") (pintype "passive"))
    )
    (net (code "64") (name "RST12") (class "Default")
      (node (ref "BM12") (pin "28") (pinfunction "NRSTO_28") (pintype "passive"))
      (node (ref "TP12") (pin "2") (pinfunction "RST_2") (pintype "passive"))
    )
    (net (code "65") (name "VDD4") (class "Default")
      (node (ref "BM10") (pin "34") (pinfunction "VDD_34") (pintype "passive"))
      (node (ref "BM11") (pin "34") (pinfunction "VDD_34") (pintype "passive"))
      (node (ref "BM12") (pin "34") (pinfunction "VDD_34") (pintype "passive"))
      (node (ref "C187") (pin "2") (pinfunction "2_2") (pintype "passive"))
      (node (ref "C188") (pin "1") (pinfunction "1_1") (pintype "passive"))
      (node (ref "C207") (pin "2") (pinfunction "2_2") (pintype "passive"))
      (node (ref "C208") (pin "1") (pinfunction "1_1") (pintype "passive"))
      (node (ref "C218") (pin "2") (pinfunction "2_2") (pintype "passive"))
      (node (ref "C219") (pin "2") (pinfunction "2_2") (pintype "passive"))
      (node (ref "C220") (pin "2") (pinfunction "2_2") (pintype "passive"))
      (node (ref "C221") (pin "2") (pinfunction "2_2") (pintype "passive"))
      (node (ref "C222") (pin "1") (pinfunction "1_1") (pintype "passive"))
      (node (ref "C226") (pin "2") (pinfunction "2_2") (pintype "passive"))
      (node (ref "C227") (pin "1") (pinfunction "1_1") (pintype "passive"))
      (node (ref "C231") (pin "2") (pinfunction "2_2") (pintype "passive"))
      (node (ref "C232") (pin "2") (pinfunction "2_2") (pintype "passive"))
      (node (ref "C233") (pin "2") (pinfunction "2_2") (pintype "passive"))
      (node (ref "C234") (pin "2") (pinfunction "2_2") (pintype "passive"))
      (node (ref "C235") (pin "1") (pinfunction "1_1") (pintype "passive"))
      (node (ref "C236") (pin "2") (pinfunction "2_2") (pintype "passive"))
      (node (ref "C237") (pin "2") (pinfunction "2_2") (pintype "passive"))
      (node (ref "C238") (pin "2") (pinfunction "2_2") (pintype "passive"))
      (node (ref "C239") (pin "2") (pinfunction "2_2") (pintype "passive"))
      (node (ref "C240") (pin "1") (pinfunction "1_1") (pintype "passive"))
      (node (ref "R166") (pin "2") (pinfunction "2_2") (pintype "passive"))
      (node (ref "R167") (pin "2") (pinfunction "2_2") (pintype "passive"))
    )
    (net (code "66") (name "unconnected-(BM10-PIN_MODE-Pad20)") (class "Default")
      (node (ref "BM10") (pin "20") (pinfunction "PIN_MODE_20") (pintype "passive+no_connect"))
    )
    (net (code "67") (name "unconnected-(BM10-RF-Pad23)") (class "Default")
      (node (ref "BM10") (pin "23") (pinfunction "RF_23") (pintype "passive+no_connect"))
    )
    (net (code "68") (name "unconnected-(BM10-TEMP_N-Pad21)") (class "Default")
      (node (ref "BM10") (pin "21") (pinfunction "TEMP_N_21") (pintype "passive+no_connect"))
    )
    (net (code "69") (name "unconnected-(BM10-TEMP_P-Pad22)") (class "Default")
      (node (ref "BM10") (pin "22") (pinfunction "TEMP_P_22") (pintype "passive+no_connect"))
    )
    (net (code "70") (name "unconnected-(BM10-TEST-Pad7)") (class "Default")
      (node (ref "BM10") (pin "7") (pinfunction "TEST_7") (pintype "passive+no_connect"))
    )
    (net (code "71") (name "unconnected-(BM10-TF-Pad24)") (class "Default")
      (node (ref "BM10") (pin "24") (pinfunction "TF_24") (pintype "passive+no_connect"))
    )
    (net (code "72") (name "unconnected-(BM11-PIN_MODE-Pad20)") (class "Default")
      (node (ref "BM11") (pin "20") (pinfunction "PIN_MODE_20") (pintype "passive+no_connect"))
    )
    (net (code "73") (name "unconnected-(BM11-RF-Pad23)") (class "Default")
      (node (ref "BM11") (pin "23") (pinfunction "RF_23") (pintype "passive+no_connect"))
    )
    (net (code "74") (name "unconnected-(BM11-TEMP_N-Pad21)") (class "Default")
      (node (ref "BM11") (pin "21") (pinfunction "TEMP_N_21") (pintype "passive+no_connect"))
    )
    (net (code "75") (name "unconnected-(BM11-TEMP_P-Pad22)") (class "Default")
      (node (ref "BM11") (pin "22") (pinfunction "TEMP_P_22") (pintype "passive+no_connect"))
    )
    (net (code "76") (name "unconnected-(BM11-TEST-Pad7)") (class "Default")
      (node (ref "BM11") (pin "7") (pinfunction "TEST_7") (pintype "passive+no_connect"))
    )
    (net (code "77") (name "unconnected-(BM11-TF-Pad24)") (class "Default")
      (node (ref "BM11") (pin "24") (pinfunction "TF_24") (pintype "passive+no_connect"))
    )
    (net (code "78") (name "unconnected-(BM12-PIN_MODE-Pad20)") (class "Default")
      (node (ref "BM12") (pin "20") (pinfunction "PIN_MODE_20") (pintype "passive+no_connect"))
    )
    (net (code "79") (name "unconnected-(BM12-RF-Pad23)") (class "Default")
      (node (ref "BM12") (pin "23") (pinfunction "RF_23") (pintype "passive+no_connect"))
    )
    (net (code "80") (name "unconnected-(BM12-TEMP_N-Pad21)") (class "Default")
      (node (ref "BM12") (pin "21") (pinfunction "TEMP_N_21") (pintype "passive+no_connect"))
    )
    (net (code "81") (name "unconnected-(BM12-TEMP_P-Pad22)") (class "Default")
      (node (ref "BM12") (pin "22") (pinfunction "TEMP_P_22") (pintype "passive+no_connect"))
    )
    (net (code "82") (name "unconnected-(BM12-TEST-Pad7)") (class "Default")
      (node (ref "BM12") (pin "7") (pinfunction "TEST_7") (pintype "passive+no_connect"))
    )
    (net (code "83") (name "unconnected-(BM12-TF-Pad24)") (class "Default")
      (node (ref "BM12") (pin "24") (pinfunction "TF_24") (pintype "passive+no_connect"))
    )
  )
)
